# irs-v8.net
KiCad netlist of a schematic drawn in EAGLE
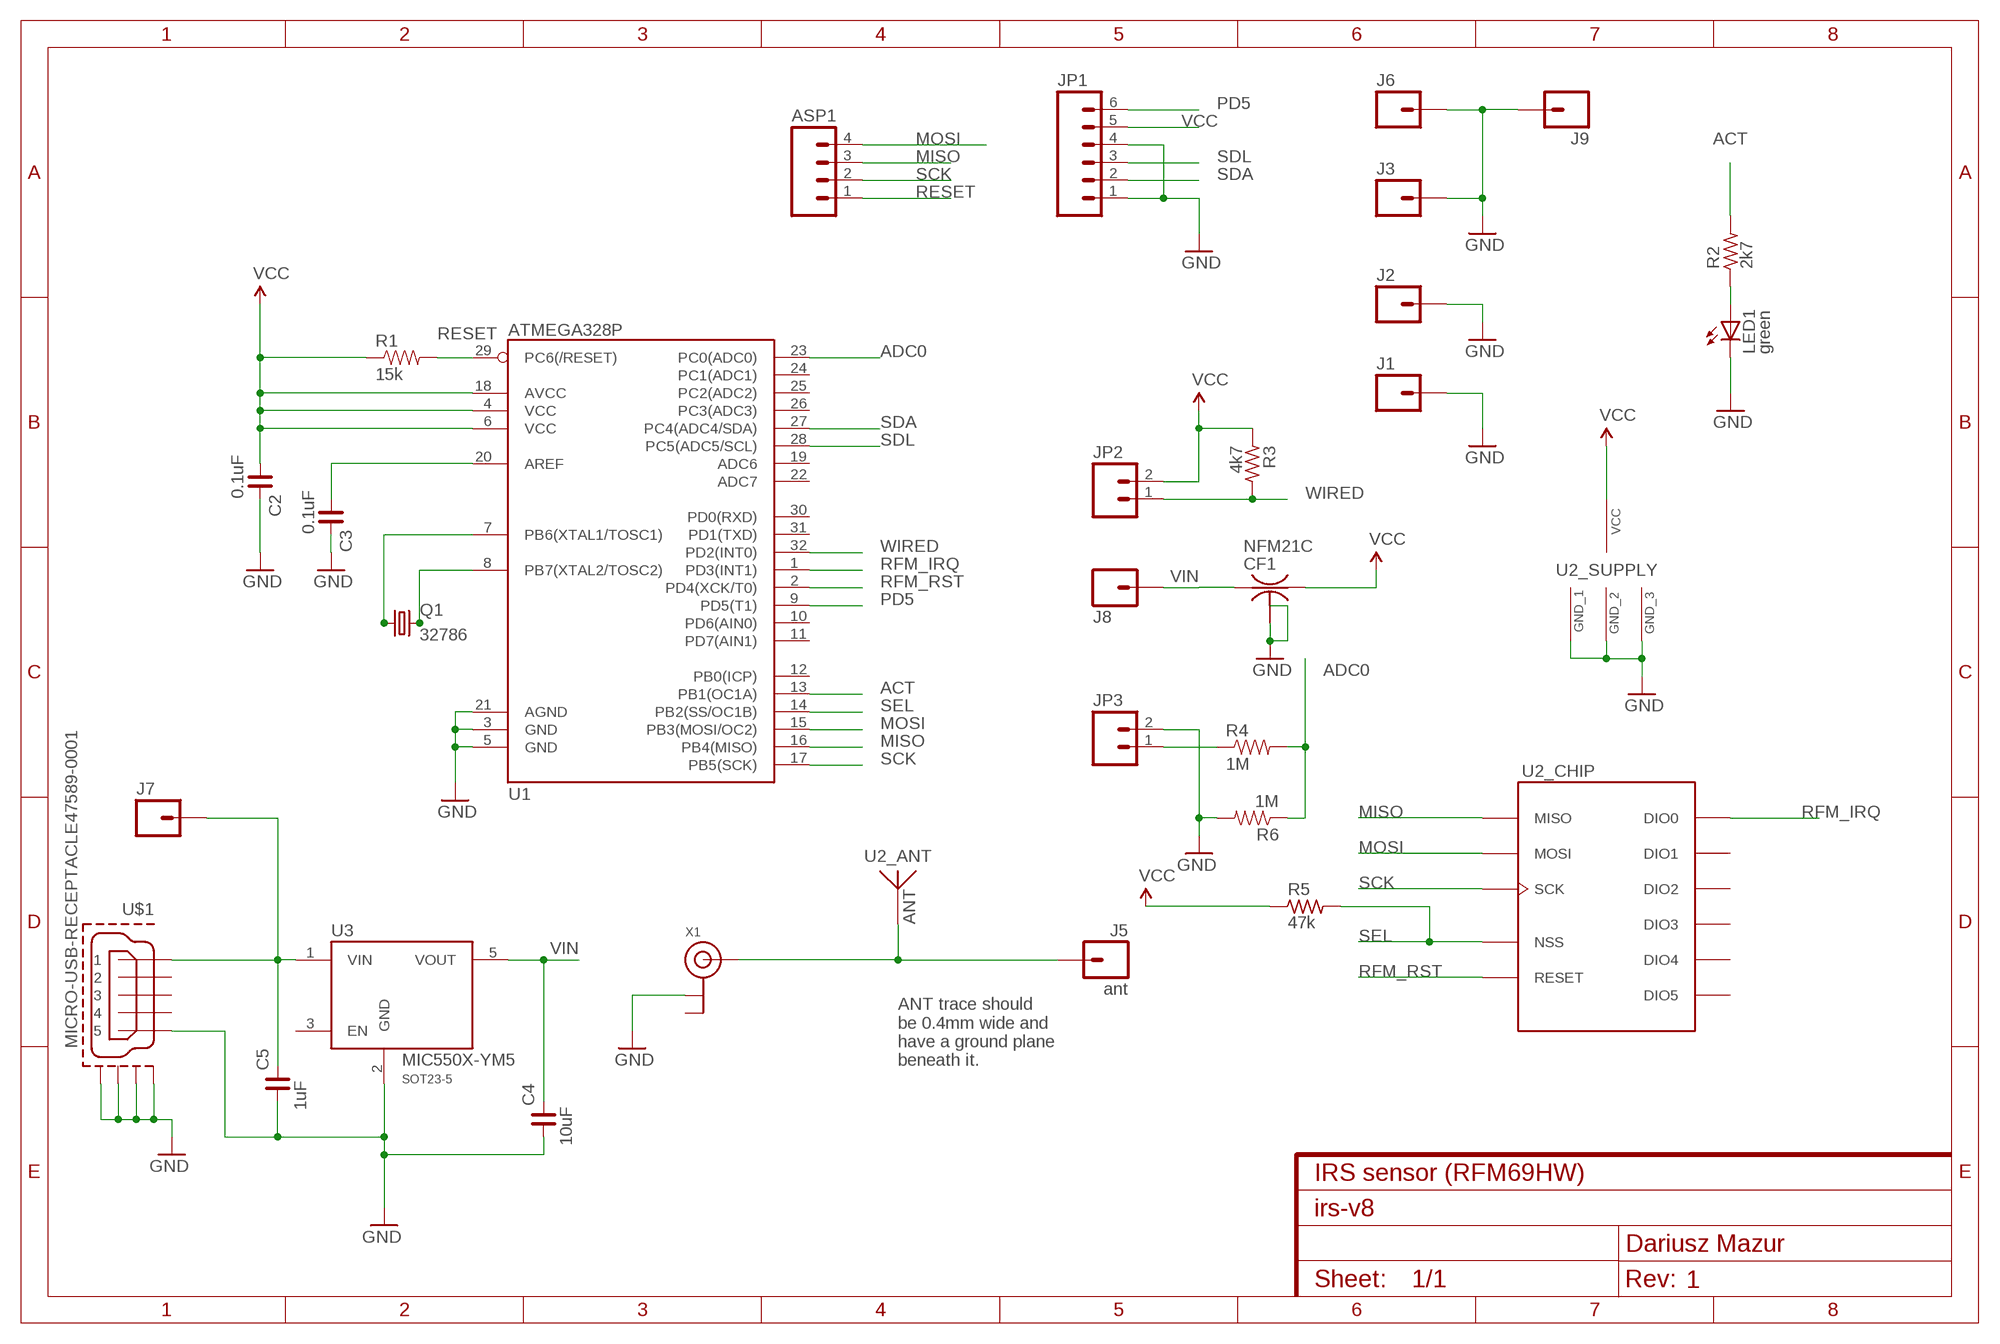
[diagram p0: schematic, sheet 1]

(export (version "E")
  (design (tool "Eeschema 10.0.6"))
  (components
    (comp (ref "ASP1")
      (value "M04NO_SILK_ALL_ROUND")
      (footprint "eagle-import:1X04_NO_SILK_ALL_ROUND")
      (libsource (lib "eagle-import") (part "M04NO_SILK_ALL_ROUND"))
    )
    (comp (ref "C2")
      (value "0.1uF")
      (footprint "eagle-import:C0603")
      (libsource (lib "eagle-import") (part "C_0603"))
    )
    (comp (ref "C3")
      (value "0.1uF")
      (footprint "eagle-import:C0603")
      (libsource (lib "eagle-import") (part "C_0603"))
    )
    (comp (ref "C4")
      (value "10uF")
      (footprint "eagle-import:C0805")
      (libsource (lib "eagle-import") (part "C_0805"))
    )
    (comp (ref "C5")
      (value "1uF")
      (footprint "eagle-import:C0805")
      (libsource (lib "eagle-import") (part "C_0805"))
    )
    (comp (ref "CF1")
      (value "NFM21C")
      (footprint "eagle-import:NFM21C")
      (fields (field (name "MPN") "NFM21CC102R1H3D"))
      (libsource (lib "eagle-import") (part "NFM21C"))
    )
    (comp (ref "J1")
      (value "M01PTH_NO_SILK_YES_STOP")
      (footprint "eagle-import:1X01_NO_SILK")
      (libsource (lib "eagle-import") (part "M01PTH_NO_SILK_YES_STOP"))
    )
    (comp (ref "J2")
      (value "M01PTH_NO_SILK_YES_STOP")
      (footprint "eagle-import:1X01_NO_SILK")
      (libsource (lib "eagle-import") (part "M01PTH_NO_SILK_YES_STOP"))
    )
    (comp (ref "J3")
      (value "M01PTH_NO_SILK_YES_STOP")
      (footprint "eagle-import:1X01_NO_SILK")
      (libsource (lib "eagle-import") (part "M01PTH_NO_SILK_YES_STOP"))
    )
    (comp (ref "J5")
      (value "ant")
      (footprint "eagle-import:1X01_NO_SILK")
      (libsource (lib "eagle-import") (part "M01PTH_NO_SILK_YES_STOP"))
    )
    (comp (ref "J6")
      (value "M01PTH_NO_SILK_YES_STOP")
      (footprint "eagle-import:1X01_NO_SILK")
      (libsource (lib "eagle-import") (part "M01PTH_NO_SILK_YES_STOP"))
    )
    (comp (ref "J7")
      (value "M01PTH_NO_SILK_YES_STOP")
      (footprint "eagle-import:1X01_NO_SILK")
      (libsource (lib "eagle-import") (part "M01PTH_NO_SILK_YES_STOP"))
    )
    (comp (ref "J8")
      (value "M01PTH_NO_SILK_YES_STOP")
      (footprint "eagle-import:1X01_NO_SILK")
      (libsource (lib "eagle-import") (part "M01PTH_NO_SILK_YES_STOP"))
    )
    (comp (ref "J9")
      (value "M01PTH_NO_SILK_YES_STOP")
      (footprint "eagle-import:1X01_NO_SILK")
      (libsource (lib "eagle-import") (part "M01PTH_NO_SILK_YES_STOP"))
    )
    (comp (ref "JP1")
      (value "M06NO_SILK_FEMALE_PTH")
      (footprint "eagle-import:1X06_NO_SILK")
      (libsource (lib "eagle-import") (part "M06NO_SILK_FEMALE_PTH"))
    )
    (comp (ref "JP2")
      (value "M021X02_NO_SILK")
      (footprint "eagle-import:1X02_NO_SILK")
      (libsource (lib "eagle-import") (part "M021X02_NO_SILK"))
    )
    (comp (ref "JP3")
      (value "M021X02_NO_SILK")
      (footprint "eagle-import:1X02_NO_SILK")
      (libsource (lib "eagle-import") (part "M021X02_NO_SILK"))
    )
    (comp (ref "LED1")
      (value "green")
      (footprint "eagle-import:LED-0603")
      (libsource (lib "eagle-import") (part "LED0603"))
    )
    (comp (ref "Q1")
      (value "32786")
      (footprint "eagle-import:MC-306")
      (fields (field (name "MPN") "MC-306 60.0KHZ  100PPM ,12.5PF"))
      (libsource (lib "eagle-import") (part "MC-306"))
    )
    (comp (ref "R1")
      (value "15k")
      (footprint "eagle-import:0603-RES")
      (libsource (lib "eagle-import") (part "RESISTOR0603-RES"))
    )
    (comp (ref "R2")
      (value "2k7")
      (footprint "eagle-import:R0603")
      (libsource (lib "eagle-import") (part "R_0603"))
    )
    (comp (ref "R3")
      (value "4k7")
      (footprint "eagle-import:R0603")
      (libsource (lib "eagle-import") (part "R_0603"))
    )
    (comp (ref "R4")
      (value "1M")
      (footprint "eagle-import:0603-RES")
      (libsource (lib "eagle-import") (part "RESISTOR0603-RES"))
    )
    (comp (ref "R5")
      (value "47k")
      (footprint "eagle-import:R0603")
      (libsource (lib "eagle-import") (part "R_0603"))
    )
    (comp (ref "R6")
      (value "1M")
      (footprint "eagle-import:0603-RES")
      (libsource (lib "eagle-import") (part "RESISTOR0603-RES"))
    )
    (comp (ref "U$1")
      (value "MICRO-USB-RECEPTACLE47589-0001")
      (footprint "eagle-import:47589-0001")
      (libsource (lib "eagle-import") (part "MICRO-USB-RECEPTACLE47589-0001"))
    )
    (comp (ref "U1")
      (value "ATMEGA328P")
      (footprint "eagle-import:TQFP32-08")
      (libsource (lib "eagle-import") (part "ATMEGA328_SMT"))
    )
    (comp (ref "U2")
      (value "RFM69HCW-S2")
      (footprint "eagle-import:HOPE-RF-16")
      (libsource (lib "eagle-import") (part "RFM69HCW-S2"))
    )
    (comp (ref "U3")
      (value "MIC550X-YM5")
      (footprint "eagle-import:SOT23-5-DBV")
      (libsource (lib "eagle-import") (part "MIC550X-YM5"))
    )
    (comp (ref "X1")
      (value "ANTENNA_U.FL")
      (footprint "eagle-import:U.FL")
      (libsource (lib "eagle-import") (part "ANTENNA_U.FL"))
    )
  )
  (nets
    (net (code "1") (name "/ACT") (class "Default")
      (node (ref "R2") (pin "2") (pinfunction "2_2") (pintype "passive"))
      (node (ref "U1") (pin "13") (pinfunction "PB1(OC1A)_13") (pintype "bidirectional"))
    )
    (net (code "2") (name "/ADC0") (class "Default")
      (node (ref "R4") (pin "2") (pinfunction "2_2") (pintype "passive"))
      (node (ref "R6") (pin "1") (pinfunction "1_1") (pintype "passive"))
      (node (ref "U1") (pin "23") (pinfunction "PC0(ADC0)_23") (pintype "bidirectional"))
    )
    (net (code "3") (name "/MISO") (class "Default")
      (node (ref "ASP1") (pin "3") (pinfunction "3_3") (pintype "passive"))
      (node (ref "U1") (pin "16") (pinfunction "PB4(MISO)_16") (pintype "bidirectional"))
      (node (ref "U2") (pin "MISO") (pinfunction "MISO_MISO") (pintype "input"))
    )
    (net (code "4") (name "/MOSI") (class "Default")
      (node (ref "ASP1") (pin "4") (pinfunction "4_4") (pintype "passive"))
      (node (ref "U1") (pin "15") (pinfunction "PB3(MOSI/OC2)_15") (pintype "bidirectional"))
      (node (ref "U2") (pin "MOSI") (pinfunction "MOSI_MOSI") (pintype "output"))
    )
    (net (code "5") (name "/PD5") (class "Default")
      (node (ref "JP1") (pin "6") (pinfunction "6_6") (pintype "passive"))
      (node (ref "U1") (pin "9") (pinfunction "PD5(T1)_9") (pintype "bidirectional"))
    )
    (net (code "6") (name "/RESET") (class "Default")
      (node (ref "ASP1") (pin "1") (pinfunction "1_1") (pintype "passive"))
      (node (ref "R1") (pin "2") (pinfunction "2_2") (pintype "passive"))
      (node (ref "U1") (pin "29") (pinfunction "PC6(/RESET)_29") (pintype "bidirectional"))
    )
    (net (code "7") (name "/RFM_IRQ") (class "Default")
      (node (ref "U1") (pin "1") (pinfunction "PD3(INT1)_1") (pintype "bidirectional"))
      (node (ref "U2") (pin "DIO0") (pinfunction "DIO0_DIO0") (pintype "bidirectional"))
    )
    (net (code "8") (name "/RFM_RST") (class "Default")
      (node (ref "U1") (pin "2") (pinfunction "PD4(XCK/T0)_2") (pintype "bidirectional"))
      (node (ref "U2") (pin "RESET") (pinfunction "RESET_RESET") (pintype "bidirectional"))
    )
    (net (code "9") (name "/SCK") (class "Default")
      (node (ref "ASP1") (pin "2") (pinfunction "2_2") (pintype "passive"))
      (node (ref "U1") (pin "17") (pinfunction "PB5(SCK)_17") (pintype "bidirectional"))
      (node (ref "U2") (pin "SCK") (pinfunction "SCK_SCK") (pintype "input"))
    )
    (net (code "10") (name "/SDA") (class "Default")
      (node (ref "JP1") (pin "2") (pinfunction "2_2") (pintype "passive"))
      (node (ref "U1") (pin "27") (pinfunction "PC4(ADC4/SDA)_27") (pintype "bidirectional"))
    )
    (net (code "11") (name "/SDL") (class "Default")
      (node (ref "JP1") (pin "3") (pinfunction "3_3") (pintype "passive"))
      (node (ref "U1") (pin "28") (pinfunction "PC5(ADC5/SCL)_28") (pintype "bidirectional"))
    )
    (net (code "12") (name "/SEL") (class "Default")
      (node (ref "R5") (pin "2") (pinfunction "2_2") (pintype "passive"))
      (node (ref "U1") (pin "14") (pinfunction "PB2(SS/OC1B)_14") (pintype "bidirectional"))
      (node (ref "U2") (pin "NSS") (pinfunction "NSS_NSS") (pintype "input"))
    )
    (net (code "13") (name "/VIN") (class "Default")
      (node (ref "C4") (pin "2") (pinfunction "2_2") (pintype "passive"))
      (node (ref "CF1") (pin "1") (pinfunction "1_1") (pintype "passive"))
      (node (ref "J8") (pin "1") (pinfunction "1_1") (pintype "passive"))
      (node (ref "U3") (pin "5") (pinfunction "VOUT_5") (pintype "bidirectional"))
    )
    (net (code "14") (name "/WIRED") (class "Default")
      (node (ref "JP2") (pin "1") (pinfunction "1_1") (pintype "passive"))
      (node (ref "R3") (pin "2") (pinfunction "2_2") (pintype "passive"))
      (node (ref "U1") (pin "32") (pinfunction "PD2(INT0)_32") (pintype "bidirectional"))
    )
    (net (code "15") (name "GND") (class "Default")
      (node (ref "C2") (pin "2") (pinfunction "2_2") (pintype "passive"))
      (node (ref "C3") (pin "2") (pinfunction "2_2") (pintype "passive"))
      (node (ref "C4") (pin "1") (pinfunction "1_1") (pintype "passive"))
      (node (ref "C5") (pin "1") (pinfunction "1_1") (pintype "passive"))
      (node (ref "CF1") (pin "2@1") (pinfunction "2_2@1") (pintype "passive"))
      (node (ref "CF1") (pin "2@2") (pinfunction "2_2@2") (pintype "passive"))
      (node (ref "J1") (pin "1") (pinfunction "1_1") (pintype "passive"))
      (node (ref "J2") (pin "1") (pinfunction "1_1") (pintype "passive"))
      (node (ref "J3") (pin "1") (pinfunction "1_1") (pintype "passive"))
      (node (ref "J6") (pin "1") (pinfunction "1_1") (pintype "passive"))
      (node (ref "J9") (pin "1") (pinfunction "1_1") (pintype "passive"))
      (node (ref "JP1") (pin "1") (pinfunction "1_1") (pintype "passive"))
      (node (ref "JP1") (pin "4") (pinfunction "4_4") (pintype "passive"))
      (node (ref "JP3") (pin "2") (pinfunction "2_2") (pintype "passive"))
      (node (ref "LED1") (pin "C") (pinfunction "C_C") (pintype "passive"))
      (node (ref "R6") (pin "2") (pinfunction "2_2") (pintype "passive"))
      (node (ref "U$1") (pin "5") (pinfunction "5_5") (pintype "input"))
      (node (ref "U$1") (pin "CASING1") (pinfunction "GND1_CASING1") (pintype "bidirectional"))
      (node (ref "U$1") (pin "CASING2") (pinfunction "GND2_CASING2") (pintype "bidirectional"))
      (node (ref "U$1") (pin "CASING3") (pinfunction "GND3_CASING3") (pintype "bidirectional"))
      (node (ref "U$1") (pin "CASING4") (pinfunction "GND4_CASING4") (pintype "bidirectional"))
      (node (ref "U1") (pin "21") (pinfunction "AGND_21") (pintype "bidirectional"))
      (node (ref "U1") (pin "3") (pinfunction "GND_3") (pintype "bidirectional"))
      (node (ref "U1") (pin "5") (pinfunction "GND_5") (pintype "bidirectional"))
      (node (ref "U2") (pin "GND1") (pinfunction "GND_1_GND1") (pintype "power_in"))
      (node (ref "U2") (pin "GND2") (pinfunction "GND_2_GND2") (pintype "power_in"))
      (node (ref "U2") (pin "GND3") (pinfunction "GND_3_GND3") (pintype "power_in"))
      (node (ref "U3") (pin "2") (pinfunction "GND_2") (pintype "bidirectional"))
      (node (ref "X1") (pin "1") (pinfunction "GND_1") (pintype "passive"))
    )
    (net (code "16") (name "Net-(JP3-Pad1)") (class "Default")
      (node (ref "JP3") (pin "1") (pinfunction "1_1") (pintype "passive"))
      (node (ref "R4") (pin "1") (pinfunction "1_1") (pintype "passive"))
    )
    (net (code "17") (name "Net-(LED1-PadA)") (class "Default")
      (node (ref "LED1") (pin "A") (pinfunction "A_A") (pintype "passive"))
      (node (ref "R2") (pin "1") (pinfunction "1_1") (pintype "passive"))
    )
    (net (code "18") (name "Net-(Q1-2)") (class "Default")
      (node (ref "Q1") (pin "4") (pinfunction "2_4") (pintype "passive"))
      (node (ref "U1") (pin "8") (pinfunction "PB7(XTAL2/TOSC2)_8") (pintype "bidirectional"))
    )
    (net (code "19") (name "Net-(U1-AREF)") (class "Default")
      (node (ref "C3") (pin "1") (pinfunction "1_1") (pintype "passive"))
      (node (ref "U1") (pin "20") (pinfunction "AREF_20") (pintype "bidirectional"))
    )
    (net (code "20") (name "Net-(U1-PB6(XTAL1{slash}TOSC1))") (class "Default")
      (node (ref "Q1") (pin "1") (pinfunction "1_1") (pintype "passive"))
      (node (ref "U1") (pin "7") (pinfunction "PB6(XTAL1/TOSC1)_7") (pintype "bidirectional"))
    )
    (net (code "21") (name "Net-(U3-VIN)") (class "Default")
      (node (ref "C5") (pin "2") (pinfunction "2_2") (pintype "passive"))
      (node (ref "J7") (pin "1") (pinfunction "1_1") (pintype "passive"))
      (node (ref "U$1") (pin "1") (pinfunction "1_1") (pintype "input"))
      (node (ref "U3") (pin "1") (pinfunction "VIN_1") (pintype "bidirectional"))
    )
    (net (code "22") (name "Net-(X1-SIGNAL)") (class "Default")
      (node (ref "J5") (pin "1") (pinfunction "1_1") (pintype "passive"))
      (node (ref "U2") (pin "ANT") (pinfunction "ANT_ANT") (pintype "passive"))
      (node (ref "X1") (pin "3") (pinfunction "SIGNAL_3") (pintype "passive"))
    )
    (net (code "23") (name "VCC") (class "Default")
      (node (ref "C2") (pin "1") (pinfunction "1_1") (pintype "passive"))
      (node (ref "CF1") (pin "3") (pinfunction "3_3") (pintype "passive"))
      (node (ref "JP1") (pin "5") (pinfunction "5_5") (pintype "passive"))
      (node (ref "JP2") (pin "2") (pinfunction "2_2") (pintype "passive"))
      (node (ref "R1") (pin "1") (pinfunction "1_1") (pintype "passive"))
      (node (ref "R3") (pin "1") (pinfunction "1_1") (pintype "passive"))
      (node (ref "R5") (pin "1") (pinfunction "1_1") (pintype "passive"))
      (node (ref "U1") (pin "18") (pinfunction "AVCC_18") (pintype "bidirectional"))
      (node (ref "U1") (pin "4") (pinfunction "VCC_4") (pintype "bidirectional"))
      (node (ref "U1") (pin "6") (pinfunction "VCC_6") (pintype "bidirectional"))
      (node (ref "U2") (pin "3.3V") (pinfunction "VCC_3.3V") (pintype "power_in"))
    )
    (net (code "24") (name "unconnected-(U$1-Pad2)") (class "Default")
      (node (ref "U$1") (pin "2") (pinfunction "2_2") (pintype "input"))
    )
    (net (code "25") (name "unconnected-(U$1-Pad3)") (class "Default")
      (node (ref "U$1") (pin "3") (pinfunction "3_3") (pintype "input"))
    )
    (net (code "26") (name "unconnected-(U$1-Pad4)") (class "Default")
      (node (ref "U$1") (pin "4") (pinfunction "4_4") (pintype "input"))
    )
    (net (code "27") (name "unconnected-(U1-ADC6-Pad19)") (class "Default")
      (node (ref "U1") (pin "19") (pinfunction "ADC6_19") (pintype "bidirectional"))
    )
    (net (code "28") (name "unconnected-(U1-ADC7-Pad22)") (class "Default")
      (node (ref "U1") (pin "22") (pinfunction "ADC7_22") (pintype "bidirectional"))
    )
    (net (code "29") (name "unconnected-(U1-PB0(ICP)-Pad12)") (class "Default")
      (node (ref "U1") (pin "12") (pinfunction "PB0(ICP)_12") (pintype "bidirectional"))
    )
    (net (code "30") (name "unconnected-(U1-PC1(ADC1)-Pad24)") (class "Default")
      (node (ref "U1") (pin "24") (pinfunction "PC1(ADC1)_24") (pintype "bidirectional"))
    )
    (net (code "31") (name "unconnected-(U1-PC2(ADC2)-Pad25)") (class "Default")
      (node (ref "U1") (pin "25") (pinfunction "PC2(ADC2)_25") (pintype "bidirectional"))
    )
    (net (code "32") (name "unconnected-(U1-PC3(ADC3)-Pad26)") (class "Default")
      (node (ref "U1") (pin "26") (pinfunction "PC3(ADC3)_26") (pintype "bidirectional"))
    )
    (net (code "33") (name "unconnected-(U1-PD0(RXD)-Pad30)") (class "Default")
      (node (ref "U1") (pin "30") (pinfunction "PD0(RXD)_30") (pintype "bidirectional"))
    )
    (net (code "34") (name "unconnected-(U1-PD1(TXD)-Pad31)") (class "Default")
      (node (ref "U1") (pin "31") (pinfunction "PD1(TXD)_31") (pintype "bidirectional"))
    )
    (net (code "35") (name "unconnected-(U1-PD6(AIN0)-Pad10)") (class "Default")
      (node (ref "U1") (pin "10") (pinfunction "PD6(AIN0)_10") (pintype "bidirectional"))
    )
    (net (code "36") (name "unconnected-(U1-PD7(AIN1)-Pad11)") (class "Default")
      (node (ref "U1") (pin "11") (pinfunction "PD7(AIN1)_11") (pintype "bidirectional"))
    )
    (net (code "37") (name "unconnected-(U2-PadDIO1)") (class "Default")
      (node (ref "U2") (pin "DIO1") (pinfunction "DIO1_DIO1") (pintype "bidirectional"))
    )
    (net (code "38") (name "unconnected-(U2-PadDIO2)") (class "Default")
      (node (ref "U2") (pin "DIO2") (pinfunction "DIO2_DIO2") (pintype "bidirectional"))
    )
    (net (code "39") (name "unconnected-(U2-PadDIO3)") (class "Default")
      (node (ref "U2") (pin "DIO3") (pinfunction "DIO3_DIO3") (pintype "bidirectional"))
    )
    (net (code "40") (name "unconnected-(U2-PadDIO4)") (class "Default")
      (node (ref "U2") (pin "DIO4") (pinfunction "DIO4_DIO4") (pintype "bidirectional"))
    )
    (net (code "41") (name "unconnected-(U2-PadDIO5)") (class "Default")
      (node (ref "U2") (pin "DIO5") (pinfunction "DIO5_DIO5") (pintype "bidirectional"))
    )
    (net (code "42") (name "unconnected-(U3-EN-Pad3)") (class "Default")
      (node (ref "U3") (pin "3") (pinfunction "EN_3") (pintype "bidirectional"))
    )
    (net (code "43") (name "unconnected-(X1-GND-Pad2)") (class "Default")
      (node (ref "X1") (pin "2") (pinfunction "GND_2") (pintype "passive"))
    )
  )
)
